# Motor_Outputs.net
KiCad netlist of a schematic drawn in Altium Designer
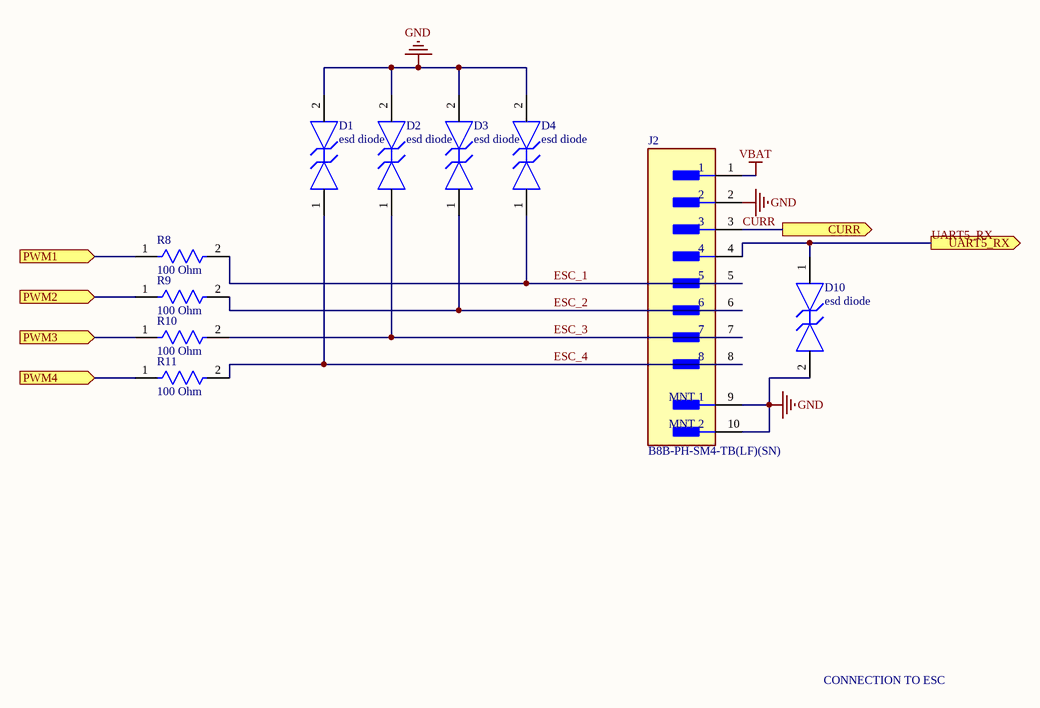
[diagram p0: Motor_Outputs.SchDoc]

(export (version "E")
  (design (tool "Eeschema 10.0.6"))
  (components
    (comp (ref "D1")
      (value "esd diode")
      (footprint "FP-152AF-MFG")
      (description "TVS DIODE 5.3V 14V 2X3DFN")
      (libsource (lib "Altium Content Vault") (part "9a4650ba5e636bd8b2e4c4fb393e9aa"))
    )
    (comp (ref "D2")
      (value "esd diode")
      (footprint "FP-152AF-MFG")
      (description "TVS DIODE 5.3V 14V 2X3DFN")
      (libsource (lib "Altium Content Vault") (part "9a4650ba5e636bd8b2e4c4fb393e9aa"))
    )
    (comp (ref "D3")
      (value "esd diode")
      (footprint "FP-152AF-MFG")
      (description "TVS DIODE 5.3V 14V 2X3DFN")
      (libsource (lib "Altium Content Vault") (part "9a4650ba5e636bd8b2e4c4fb393e9aa"))
    )
    (comp (ref "D4")
      (value "esd diode")
      (footprint "FP-152AF-MFG")
      (description "TVS DIODE 5.3V 14V 2X3DFN")
      (libsource (lib "Altium Content Vault") (part "9a4650ba5e636bd8b2e4c4fb393e9aa"))
    )
    (comp (ref "D10")
      (value "esd diode")
      (footprint "FP-152AF-MFG")
      (description "TVS DIODE 5.3V 14V 2X3DFN")
      (libsource (lib "Altium Content Vault") (part "9a4650ba5e636bd8b2e4c4fb393e9aa"))
    )
    (comp (ref "J2")
      (value "B8B-PH-SM4-TB(LF)(SN)")
      (footprint "FP-B8B-PH-SM4-TB_LF_SN-MFG")
      (description "CONN HEADER SMD 8POS 2MM")
      (libsource (lib "Altium Content Vault") (part "c99efc1074d36b7f406f17bfcf6f1d6"))
    )
    (comp (ref "R8")
      (value "100 Ohm")
      (footprint "FP-MCS0402-IPC_A")
      (description "RES SMD 1.2K OHM 1% 1/10W 0402")
      (fields (field (name "TOLERANCE") "0.5%"))
      (libsource (lib "Altium Content Vault") (part "1029c3af85768c4190bb7ad29bc67b5"))
    )
    (comp (ref "R9")
      (value "100 Ohm")
      (footprint "FP-MCS0402-IPC_A")
      (description "RES SMD 1.2K OHM 1% 1/10W 0402")
      (fields (field (name "TOLERANCE") "0.5%"))
      (libsource (lib "Altium Content Vault") (part "1029c3af85768c4190bb7ad29bc67b5"))
    )
    (comp (ref "R10")
      (value "100 Ohm")
      (footprint "FP-MCS0402-IPC_A")
      (description "RES SMD 1.2K OHM 1% 1/10W 0402")
      (fields (field (name "TOLERANCE") "0.5%"))
      (libsource (lib "Altium Content Vault") (part "1029c3af85768c4190bb7ad29bc67b5"))
    )
    (comp (ref "R11")
      (value "100 Ohm")
      (footprint "FP-MCS0402-IPC_A")
      (description "RES SMD 1.2K OHM 1% 1/10W 0402")
      (fields (field (name "TOLERANCE") "0.5%"))
      (libsource (lib "Altium Content Vault") (part "1029c3af85768c4190bb7ad29bc67b5"))
    )
  )
  (nets
    (net (code "1") (name "/CURR") (class "Default")
      (node (ref "J2") (pin "3") (pinfunction "3_3") (pintype "passive"))
    )
    (net (code "2") (name "/ESC_1") (class "Default")
      (node (ref "D4") (pin "1") (pinfunction "1_1") (pintype "passive"))
      (node (ref "J2") (pin "5") (pinfunction "5_5") (pintype "passive"))
      (node (ref "R8") (pin "2") (pinfunction "2_2") (pintype "passive"))
    )
    (net (code "3") (name "/ESC_2") (class "Default")
      (node (ref "D3") (pin "1") (pinfunction "1_1") (pintype "passive"))
      (node (ref "J2") (pin "6") (pinfunction "6_6") (pintype "passive"))
      (node (ref "R9") (pin "2") (pinfunction "2_2") (pintype "passive"))
    )
    (net (code "4") (name "/ESC_3") (class "Default")
      (node (ref "D2") (pin "1") (pinfunction "1_1") (pintype "passive"))
      (node (ref "J2") (pin "7") (pinfunction "7_7") (pintype "passive"))
      (node (ref "R10") (pin "2") (pinfunction "2_2") (pintype "passive"))
    )
    (net (code "5") (name "/ESC_4") (class "Default")
      (node (ref "D1") (pin "1") (pinfunction "1_1") (pintype "passive"))
      (node (ref "J2") (pin "8") (pinfunction "8_8") (pintype "passive"))
      (node (ref "R11") (pin "2") (pinfunction "2_2") (pintype "passive"))
    )
    (net (code "6") (name "/PWM1") (class "Default")
      (node (ref "R8") (pin "1") (pinfunction "1_1") (pintype "passive"))
    )
    (net (code "7") (name "/PWM2") (class "Default")
      (node (ref "R9") (pin "1") (pinfunction "1_1") (pintype "passive"))
    )
    (net (code "8") (name "/PWM3") (class "Default")
      (node (ref "R10") (pin "1") (pinfunction "1_1") (pintype "passive"))
    )
    (net (code "9") (name "/PWM4") (class "Default")
      (node (ref "R11") (pin "1") (pinfunction "1_1") (pintype "passive"))
    )
    (net (code "10") (name "/UART5_RX") (class "Default")
      (node (ref "D10") (pin "1") (pinfunction "1_1") (pintype "passive"))
      (node (ref "J2") (pin "4") (pinfunction "4_4") (pintype "passive"))
    )
    (net (code "11") (name "GND") (class "Default")
      (node (ref "D1") (pin "2") (pinfunction "2_2") (pintype "passive"))
      (node (ref "D10") (pin "2") (pinfunction "2_2") (pintype "passive"))
      (node (ref "D2") (pin "2") (pinfunction "2_2") (pintype "passive"))
      (node (ref "D3") (pin "2") (pinfunction "2_2") (pintype "passive"))
      (node (ref "D4") (pin "2") (pinfunction "2_2") (pintype "passive"))
      (node (ref "J2") (pin "10") (pinfunction "MNT_2_10") (pintype "passive"))
      (node (ref "J2") (pin "2") (pinfunction "2_2") (pintype "passive"))
      (node (ref "J2") (pin "9") (pinfunction "MNT_1_9") (pintype "passive"))
    )
    (net (code "12") (name "VBAT") (class "Default")
      (node (ref "J2") (pin "1") (pinfunction "1_1") (pintype "passive"))
    )
  )
)
